# Filter-18.net
KiCad netlist of a schematic drawn in Altium Designer
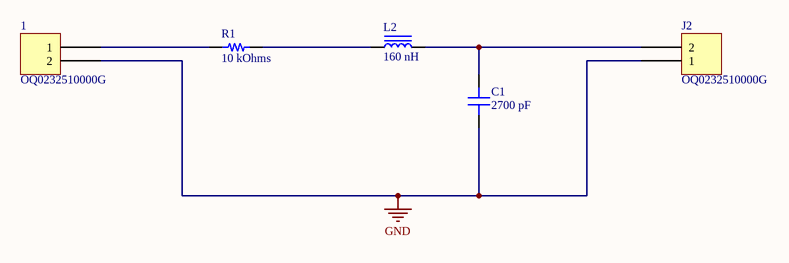
[diagram p0: Filter-18.SchDoc]

(export (version "E")
  (design (tool "Eeschema 10.0.6"))
  (components
    (comp (ref "1")
      (value "OQ0232510000G")
      (footprint "FCI 06-381-2PIN")
      (description "TERM BLOCK HDR 2POS 90DEG 3.81MM")
      (fields (field (name "MANUFACTURER") "Amphenol Anytek"))
      (libsource (lib "") (part "2 Pin_1"))
    )
    (comp (ref "C1")
      (value "2700 pF")
      (footprint "CAP 0603_1608")
      (description "CAP CER 2700PF 25V NP0 0603")
      (fields (field (name "PART NUMBER") "C0603C272F3GAC7867") (field (name "MANUFACTURER") "KEMET"))
      (libsource (lib "Celestial Altium Library - altium_library") (part "Capacitor"))
    )
    (comp (ref "J2")
      (value "OQ0232510000G")
      (footprint "FCI 06-381-2PIN")
      (description "TERM BLOCK HDR 2POS 90DEG 3.81MM")
      (fields (field (name "MANUFACTURER") "Amphenol Anytek"))
      (libsource (lib "Celestial Altium Library - altium_library") (part "2 Pin"))
    )
    (comp (ref "L2")
      (value "160 nH")
      (footprint "IND 0402_1005 RF WW")
      (description "FIXED IND 160NH 480MA 330MOHM SM")
      (fields
        (field (name "PART NUMBER") "LQW15CNR16J00D")
        (field (name "MANUFACTURER") "Murata Electronics")
      )
      (libsource (lib "Celestial Altium Library - altium_library") (part "Inductor"))
    )
    (comp (ref "R1")
      (value "10 kOhms")
      (footprint "RES 0603_1608")
      (description "RES 10K OHM 0.1% 1/16W 0603")
      (fields
        (field (name "PART NUMBER") "RNCS0603BKE10K0")
        (field (name "MANUFACTURER") "Stackpole Electronics Inc")
      )
      (libsource (lib "Celestial Altium Library - altium_library") (part "Resistor"))
    )
  )
  (nets
    (net (code "1") (name "GND") (class "Default")
      (node (ref "1") (pin "2") (pinfunction "2_2") (pintype "passive"))
      (node (ref "C1") (pin "1") (pinfunction "1_1") (pintype "passive"))
      (node (ref "J2") (pin "1") (pinfunction "1_1") (pintype "passive"))
    )
    (net (code "2") (name "Net-(1-Pad1)") (class "Default")
      (node (ref "1") (pin "1") (pinfunction "1_1") (pintype "passive"))
      (node (ref "R1") (pin "1") (pinfunction "1_1") (pintype "passive"))
    )
    (net (code "3") (name "Net-(C1-Pad2)") (class "Default")
      (node (ref "C1") (pin "2") (pinfunction "2_2") (pintype "passive"))
      (node (ref "J2") (pin "2") (pinfunction "2_2") (pintype "passive"))
      (node (ref "L2") (pin "2") (pinfunction "2_2") (pintype "passive"))
    )
    (net (code "4") (name "Net-(L2-Pad1)") (class "Default")
      (node (ref "L2") (pin "1") (pinfunction "1_1") (pintype "passive"))
      (node (ref "R1") (pin "2") (pinfunction "2_2") (pintype "passive"))
    )
  )
)
